# voltage_difference_detector.net
KiCad netlist of a schematic drawn in EAGLE
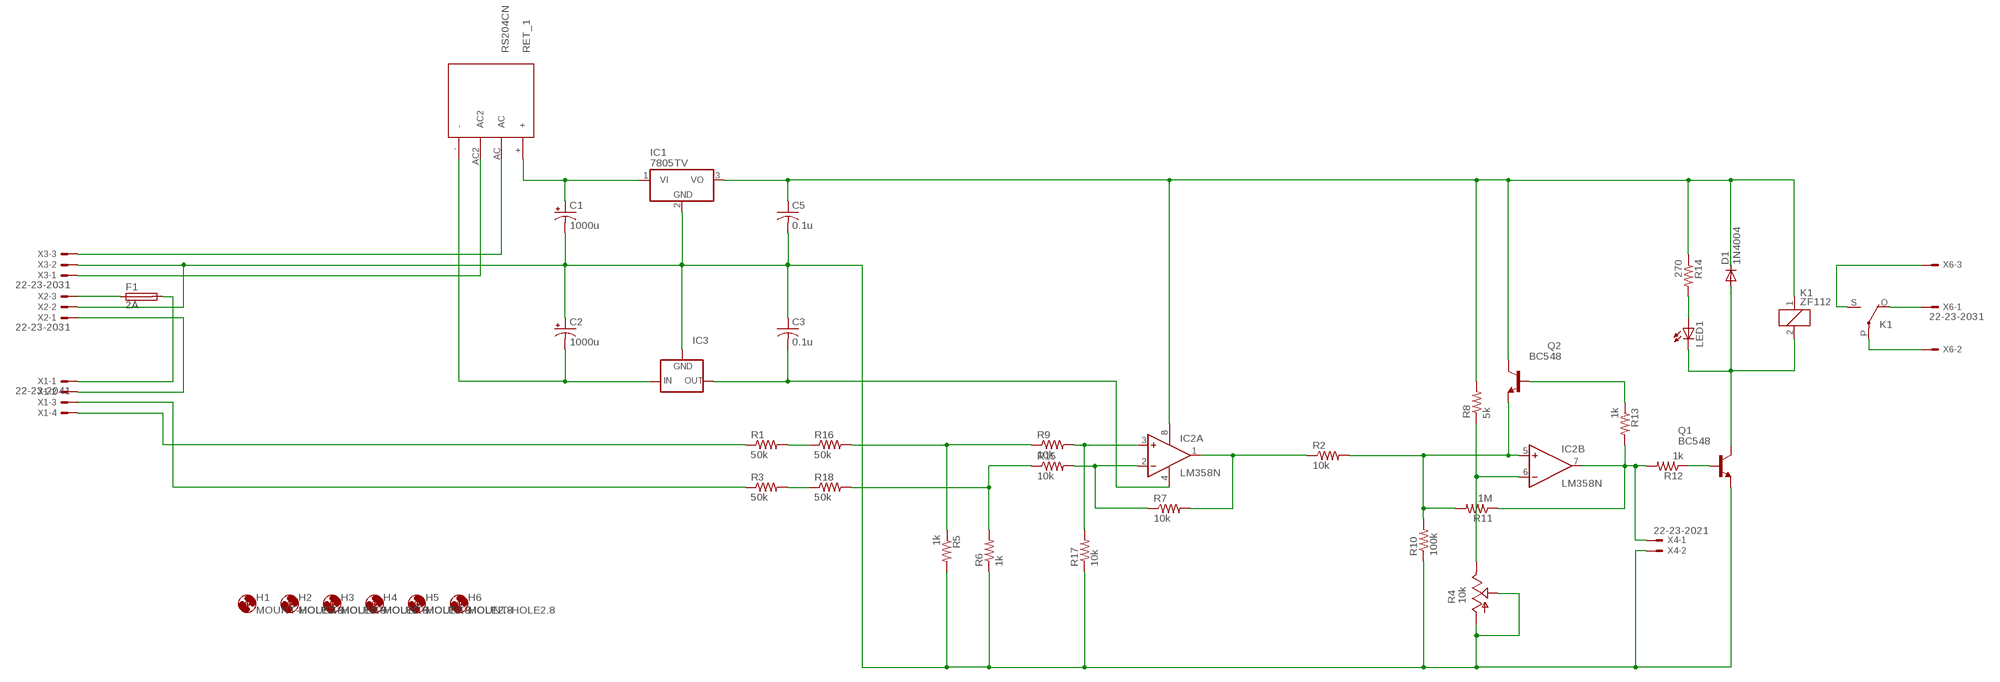
[diagram p0: schematic, sheet 1]

(export (version "E")
  (design (tool "Eeschema 10.0.6"))
  (components
    (comp (ref "C1")
      (value "1000u")
      (footprint "eagle-import:E5-10,5")
      (libsource (lib "eagle-import") (part "CPOL-USE5-10.5"))
    )
    (comp (ref "C2")
      (value "1000u")
      (footprint "eagle-import:E5-10,5")
      (libsource (lib "eagle-import") (part "CPOL-USE5-10.5"))
    )
    (comp (ref "C3")
      (value "0.1u")
      (footprint "eagle-import:C050-024X044")
      (libsource (lib "eagle-import") (part "C-US050-024X044"))
    )
    (comp (ref "C5")
      (value "0.1u")
      (footprint "eagle-import:C050-024X044")
      (libsource (lib "eagle-import") (part "C-US050-024X044"))
    )
    (comp (ref "D1")
      (value "1N4004")
      (footprint "eagle-import:DO41-10")
      (libsource (lib "eagle-import") (part "1N4004"))
    )
    (comp (ref "F1")
      (value "2A")
      (footprint "eagle-import:SH22,5")
      (fields (field (name "MF") "SCHURTER") (field (name "MPN") "0031.8201"))
      (libsource (lib "eagle-import") (part "SH22,5"))
    )
    (comp (ref "H1")
      (value "MOUNT-HOLE2.8")
      (footprint "eagle-import:2,8")
      (libsource (lib "eagle-import") (part "MOUNT-HOLE2.8"))
    )
    (comp (ref "H2")
      (value "MOUNT-HOLE2.8")
      (footprint "eagle-import:2,8")
      (libsource (lib "eagle-import") (part "MOUNT-HOLE2.8"))
    )
    (comp (ref "H3")
      (value "MOUNT-HOLE2.8")
      (footprint "eagle-import:2,8")
      (libsource (lib "eagle-import") (part "MOUNT-HOLE2.8"))
    )
    (comp (ref "H4")
      (value "MOUNT-HOLE2.8")
      (footprint "eagle-import:2,8")
      (libsource (lib "eagle-import") (part "MOUNT-HOLE2.8"))
    )
    (comp (ref "H5")
      (value "MOUNT-HOLE2.8")
      (footprint "eagle-import:2,8")
      (libsource (lib "eagle-import") (part "MOUNT-HOLE2.8"))
    )
    (comp (ref "H6")
      (value "MOUNT-HOLE2.8")
      (footprint "eagle-import:2,8")
      (libsource (lib "eagle-import") (part "MOUNT-HOLE2.8"))
    )
    (comp (ref "IC1")
      (value "7805TV")
      (footprint "eagle-import:TO220V")
      (libsource (lib "eagle-import") (part "78TV05"))
    )
    (comp (ref "IC2")
      (value "LM358N")
      (footprint "eagle-import:DIL08")
      (libsource (lib "eagle-import") (part "LM358N"))
    )
    (comp (ref "IC3")
      (value "79XXS")
      (footprint "eagle-import:79XXS")
      (libsource (lib "eagle-import") (part "79XXS"))
    )
    (comp (ref "K1")
      (value "ZF112")
      (footprint "eagle-import:ZF112")
      (libsource (lib "eagle-import") (part "ZF112"))
    )
    (comp (ref "LED1")
      (value "LED3MM")
      (footprint "eagle-import:LED3MM")
      (libsource (lib "eagle-import") (part "LED3MM"))
    )
    (comp (ref "Q1")
      (value "BC548")
      (footprint "eagle-import:TO92-EBC")
      (libsource (lib "eagle-import") (part "BC548"))
    )
    (comp (ref "Q2")
      (value "BC548")
      (footprint "eagle-import:TO92-EBC")
      (libsource (lib "eagle-import") (part "BC548"))
    )
    (comp (ref "R1")
      (value "50k")
      (footprint "eagle-import:0204_7")
      (libsource (lib "eagle-import") (part "R-US_0204/7"))
    )
    (comp (ref "R2")
      (value "10k")
      (footprint "eagle-import:0204_7")
      (libsource (lib "eagle-import") (part "R-US_0204/7"))
    )
    (comp (ref "R3")
      (value "50k")
      (footprint "eagle-import:0204_7")
      (libsource (lib "eagle-import") (part "R-US_0204/7"))
    )
    (comp (ref "R4")
      (value "10k")
      (footprint "eagle-import:RJ9W")
      (libsource (lib "eagle-import") (part "TRIM_US-RJ9W"))
    )
    (comp (ref "R5")
      (value "1k")
      (footprint "eagle-import:0204_7")
      (libsource (lib "eagle-import") (part "R-US_0204/7"))
    )
    (comp (ref "R6")
      (value "1k")
      (footprint "eagle-import:0204_7")
      (libsource (lib "eagle-import") (part "R-US_0204/7"))
    )
    (comp (ref "R7")
      (value "10k")
      (footprint "eagle-import:0204_7")
      (libsource (lib "eagle-import") (part "R-US_0204/7"))
    )
    (comp (ref "R8")
      (value "5k")
      (footprint "eagle-import:0204_7")
      (libsource (lib "eagle-import") (part "R-US_0204/7"))
    )
    (comp (ref "R9")
      (value "10k")
      (footprint "eagle-import:0204_7")
      (libsource (lib "eagle-import") (part "R-US_0204/7"))
    )
    (comp (ref "R10")
      (value "100k")
      (footprint "eagle-import:0204_7")
      (libsource (lib "eagle-import") (part "R-US_0204/7"))
    )
    (comp (ref "R11")
      (value "1M")
      (footprint "eagle-import:0204_7")
      (libsource (lib "eagle-import") (part "R-US_0204/7"))
    )
    (comp (ref "R12")
      (value "1k")
      (footprint "eagle-import:0204_7")
      (libsource (lib "eagle-import") (part "R-US_0204/7"))
    )
    (comp (ref "R13")
      (value "1k")
      (footprint "eagle-import:0204_7")
      (libsource (lib "eagle-import") (part "R-US_0204/7"))
    )
    (comp (ref "R14")
      (value "270")
      (footprint "eagle-import:0204_7")
      (libsource (lib "eagle-import") (part "R-US_0204/7"))
    )
    (comp (ref "R15")
      (value "10k")
      (footprint "eagle-import:0204_7")
      (libsource (lib "eagle-import") (part "R-US_0204/7"))
    )
    (comp (ref "R16")
      (value "50k")
      (footprint "eagle-import:0204_7")
      (libsource (lib "eagle-import") (part "R-US_0204/7"))
    )
    (comp (ref "R17")
      (value "10k")
      (footprint "eagle-import:0204_7")
      (libsource (lib "eagle-import") (part "R-US_0204/7"))
    )
    (comp (ref "R18")
      (value "50k")
      (footprint "eagle-import:0204_7")
      (libsource (lib "eagle-import") (part "R-US_0204/7"))
    )
    (comp (ref "RET_1")
      (value "RS204CN")
      (footprint "eagle-import:SIP")
      (libsource (lib "eagle-import") (part "RS204CN"))
    )
    (comp (ref "X1")
      (value "22-23-2041")
      (footprint "eagle-import:22-23-2041")
      (fields (field (name "MF") "MOLEX"))
      (libsource (lib "eagle-import") (part "22-23-2041"))
    )
    (comp (ref "X2")
      (value "22-23-2031")
      (footprint "eagle-import:22-23-2031")
      (fields (field (name "MF") "MOLEX"))
      (libsource (lib "eagle-import") (part "22-23-2031"))
    )
    (comp (ref "X3")
      (value "22-23-2031")
      (footprint "eagle-import:22-23-2031")
      (fields (field (name "MF") "MOLEX"))
      (libsource (lib "eagle-import") (part "22-23-2031"))
    )
    (comp (ref "X4")
      (value "22-23-2021")
      (footprint "eagle-import:22-23-2021")
      (fields (field (name "MF") "MOLEX"))
      (libsource (lib "eagle-import") (part "22-23-2021"))
    )
    (comp (ref "X6")
      (value "22-23-2031")
      (footprint "eagle-import:22-23-2031")
      (fields (field (name "MF") "MOLEX"))
      (libsource (lib "eagle-import") (part "22-23-2031"))
    )
  )
  (nets
    (net (code "1") (name "Net-(C2-Pad-)") (class "Default")
      (node (ref "C2") (pin "-") (pinfunction "-_-") (pintype "passive"))
      (node (ref "IC3") (pin "IN") (pinfunction "IN_IN") (pintype "input"))
      (node (ref "RET_1") (pin "-") (pinfunction "-_-") (pintype "bidirectional"))
    )
    (net (code "2") (name "Net-(IC1-GND)") (class "Default")
      (node (ref "C1") (pin "-") (pinfunction "-_-") (pintype "passive"))
      (node (ref "C2") (pin "+") (pinfunction "+_+") (pintype "passive"))
      (node (ref "C3") (pin "1") (pinfunction "1_1") (pintype "passive"))
      (node (ref "C5") (pin "2") (pinfunction "2_2") (pintype "passive"))
      (node (ref "IC1") (pin "2") (pinfunction "GND_2") (pintype "passive"))
      (node (ref "IC3") (pin "GND") (pinfunction "GND_GND") (pintype "input"))
      (node (ref "Q1") (pin "E") (pinfunction "E_E") (pintype "passive"))
      (node (ref "R10") (pin "1") (pinfunction "1_1") (pintype "passive"))
      (node (ref "R17") (pin "1") (pinfunction "1_1") (pintype "passive"))
      (node (ref "R4") (pin "A") (pinfunction "A_A") (pintype "passive"))
      (node (ref "R4") (pin "S") (pinfunction "S_S") (pintype "passive"))
      (node (ref "R5") (pin "2") (pinfunction "2_2") (pintype "passive"))
      (node (ref "R6") (pin "1") (pinfunction "1_1") (pintype "passive"))
      (node (ref "X2") (pin "2") (pinfunction "S_2") (pintype "passive"))
      (node (ref "X3") (pin "2") (pinfunction "S_2") (pintype "passive"))
      (node (ref "X4") (pin "2") (pinfunction "S_2") (pintype "passive"))
    )
    (net (code "3") (name "Net-(IC1-VI)") (class "Default")
      (node (ref "C1") (pin "+") (pinfunction "+_+") (pintype "passive"))
      (node (ref "IC1") (pin "1") (pinfunction "VI_1") (pintype "input"))
      (node (ref "RET_1") (pin "+") (pinfunction "+_+") (pintype "bidirectional"))
    )
    (net (code "4") (name "Net-(IC1-VO)") (class "Default")
      (node (ref "C5") (pin "1") (pinfunction "1_1") (pintype "passive"))
      (node (ref "D1") (pin "C") (pinfunction "C_C") (pintype "passive"))
      (node (ref "IC1") (pin "3") (pinfunction "VO_3") (pintype "passive"))
      (node (ref "IC2") (pin "8") (pinfunction "V+_8") (pintype "power_in"))
      (node (ref "K1") (pin "1") (pinfunction "1_1") (pintype "passive"))
      (node (ref "Q2") (pin "C") (pinfunction "C_C") (pintype "passive"))
      (node (ref "R14") (pin "1") (pinfunction "1_1") (pintype "passive"))
      (node (ref "R8") (pin "2") (pinfunction "2_2") (pintype "passive"))
    )
    (net (code "5") (name "Net-(IC2A-+IN)") (class "Default")
      (node (ref "IC2") (pin "3") (pinfunction "+IN_3") (pintype "input"))
      (node (ref "R17") (pin "2") (pinfunction "2_2") (pintype "passive"))
      (node (ref "R9") (pin "2") (pinfunction "2_2") (pintype "passive"))
    )
    (net (code "6") (name "Net-(IC2A--IN)") (class "Default")
      (node (ref "IC2") (pin "2") (pinfunction "-IN_2") (pintype "input"))
      (node (ref "R15") (pin "2") (pinfunction "2_2") (pintype "passive"))
      (node (ref "R7") (pin "1") (pinfunction "1_1") (pintype "passive"))
    )
    (net (code "7") (name "Net-(IC2A-OUT)") (class "Default")
      (node (ref "IC2") (pin "1") (pinfunction "OUT_1") (pintype "output"))
      (node (ref "R2") (pin "1") (pinfunction "1_1") (pintype "passive"))
      (node (ref "R7") (pin "2") (pinfunction "2_2") (pintype "passive"))
    )
    (net (code "8") (name "Net-(IC2B-+IN)") (class "Default")
      (node (ref "IC2") (pin "5") (pinfunction "+IN_5") (pintype "input"))
      (node (ref "Q2") (pin "E") (pinfunction "E_E") (pintype "passive"))
      (node (ref "R10") (pin "2") (pinfunction "2_2") (pintype "passive"))
      (node (ref "R11") (pin "2") (pinfunction "2_2") (pintype "passive"))
      (node (ref "R2") (pin "2") (pinfunction "2_2") (pintype "passive"))
    )
    (net (code "9") (name "Net-(IC2B--IN)") (class "Default")
      (node (ref "IC2") (pin "6") (pinfunction "-IN_6") (pintype "input"))
      (node (ref "R4") (pin "E") (pinfunction "E_E") (pintype "passive"))
      (node (ref "R8") (pin "1") (pinfunction "1_1") (pintype "passive"))
    )
    (net (code "10") (name "Net-(IC2B-OUT)") (class "Default")
      (node (ref "IC2") (pin "7") (pinfunction "OUT_7") (pintype "output"))
      (node (ref "R11") (pin "1") (pinfunction "1_1") (pintype "passive"))
      (node (ref "R12") (pin "2") (pinfunction "2_2") (pintype "passive"))
      (node (ref "R13") (pin "2") (pinfunction "2_2") (pintype "passive"))
      (node (ref "X4") (pin "1") (pinfunction "S_1") (pintype "passive"))
    )
    (net (code "11") (name "Net-(IC2C-V-)") (class "Default")
      (node (ref "C3") (pin "2") (pinfunction "2_2") (pintype "passive"))
      (node (ref "IC2") (pin "4") (pinfunction "V-_4") (pintype "power_in"))
      (node (ref "IC3") (pin "OUT") (pinfunction "OUT_OUT") (pintype "passive"))
    )
    (net (code "12") (name "Net-(LED1-C)") (class "Default")
      (node (ref "D1") (pin "A") (pinfunction "A_A") (pintype "passive"))
      (node (ref "K1") (pin "2") (pinfunction "2_2") (pintype "passive"))
      (node (ref "LED1") (pin "K") (pinfunction "C_K") (pintype "passive"))
      (node (ref "Q1") (pin "C") (pinfunction "C_C") (pintype "passive"))
    )
    (net (code "13") (name "Net-(LED1-PadA)") (class "Default")
      (node (ref "LED1") (pin "A") (pinfunction "A_A") (pintype "passive"))
      (node (ref "R14") (pin "2") (pinfunction "2_2") (pintype "passive"))
    )
    (net (code "14") (name "Net-(Q1-PadB)") (class "Default")
      (node (ref "Q1") (pin "B") (pinfunction "B_B") (pintype "passive"))
      (node (ref "R12") (pin "1") (pinfunction "1_1") (pintype "passive"))
    )
    (net (code "15") (name "Net-(Q2-PadB)") (class "Default")
      (node (ref "Q2") (pin "B") (pinfunction "B_B") (pintype "passive"))
      (node (ref "R13") (pin "1") (pinfunction "1_1") (pintype "passive"))
    )
    (net (code "16") (name "Net-(R1-Pad2)") (class "Default")
      (node (ref "R1") (pin "2") (pinfunction "2_2") (pintype "passive"))
      (node (ref "R16") (pin "1") (pinfunction "1_1") (pintype "passive"))
    )
    (net (code "17") (name "Net-(R15-Pad1)") (class "Default")
      (node (ref "R15") (pin "1") (pinfunction "1_1") (pintype "passive"))
      (node (ref "R18") (pin "2") (pinfunction "2_2") (pintype "passive"))
      (node (ref "R6") (pin "2") (pinfunction "2_2") (pintype "passive"))
    )
    (net (code "18") (name "Net-(R16-Pad2)") (class "Default")
      (node (ref "R16") (pin "2") (pinfunction "2_2") (pintype "passive"))
      (node (ref "R5") (pin "1") (pinfunction "1_1") (pintype "passive"))
      (node (ref "R9") (pin "1") (pinfunction "1_1") (pintype "passive"))
    )
    (net (code "19") (name "Net-(R18-Pad1)") (class "Default")
      (node (ref "R18") (pin "1") (pinfunction "1_1") (pintype "passive"))
      (node (ref "R3") (pin "2") (pinfunction "2_2") (pintype "passive"))
    )
    (net (code "20") (name "Net-(X1A-S)") (class "Default")
      (node (ref "F1") (pin "2") (pinfunction "2_2") (pintype "passive"))
      (node (ref "X1") (pin "1") (pinfunction "S_1") (pintype "passive"))
    )
    (net (code "21") (name "Net-(X1B-S)") (class "Default")
      (node (ref "X1") (pin "2") (pinfunction "S_2") (pintype "passive"))
      (node (ref "X2") (pin "1") (pinfunction "S_1") (pintype "passive"))
    )
    (net (code "22") (name "Net-(X1C-S)") (class "Default")
      (node (ref "R3") (pin "1") (pinfunction "1_1") (pintype "passive"))
      (node (ref "X1") (pin "3") (pinfunction "S_3") (pintype "passive"))
    )
    (net (code "23") (name "Net-(X1D-S)") (class "Default")
      (node (ref "R1") (pin "1") (pinfunction "1_1") (pintype "passive"))
      (node (ref "X1") (pin "4") (pinfunction "S_4") (pintype "passive"))
    )
    (net (code "24") (name "Net-(X2C-S)") (class "Default")
      (node (ref "F1") (pin "1") (pinfunction "1_1") (pintype "passive"))
      (node (ref "X2") (pin "3") (pinfunction "S_3") (pintype "passive"))
    )
    (net (code "25") (name "Net-(X3A-S)") (class "Default")
      (node (ref "RET_1") (pin "AC2") (pinfunction "AC2_AC2") (pintype "bidirectional"))
      (node (ref "X3") (pin "1") (pinfunction "S_1") (pintype "passive"))
    )
    (net (code "26") (name "Net-(X3C-S)") (class "Default")
      (node (ref "RET_1") (pin "AC") (pinfunction "AC_AC") (pintype "bidirectional"))
      (node (ref "X3") (pin "3") (pinfunction "S_3") (pintype "passive"))
    )
    (net (code "27") (name "Net-(X6A-S)") (class "Default")
      (node (ref "K1") (pin "O") (pinfunction "O_O") (pintype "passive"))
      (node (ref "X6") (pin "1") (pinfunction "S_1") (pintype "passive"))
    )
    (net (code "28") (name "Net-(X6B-S)") (class "Default")
      (node (ref "K1") (pin "P") (pinfunction "P_P") (pintype "passive"))
      (node (ref "X6") (pin "2") (pinfunction "S_2") (pintype "passive"))
    )
    (net (code "29") (name "Net-(X6C-S)") (class "Default")
      (node (ref "K1") (pin "S") (pinfunction "S_S") (pintype "passive"))
      (node (ref "X6") (pin "3") (pinfunction "S_3") (pintype "passive"))
    )
  )
)
